# MPPT2.net
KiCad netlist of a schematic drawn in EAGLE
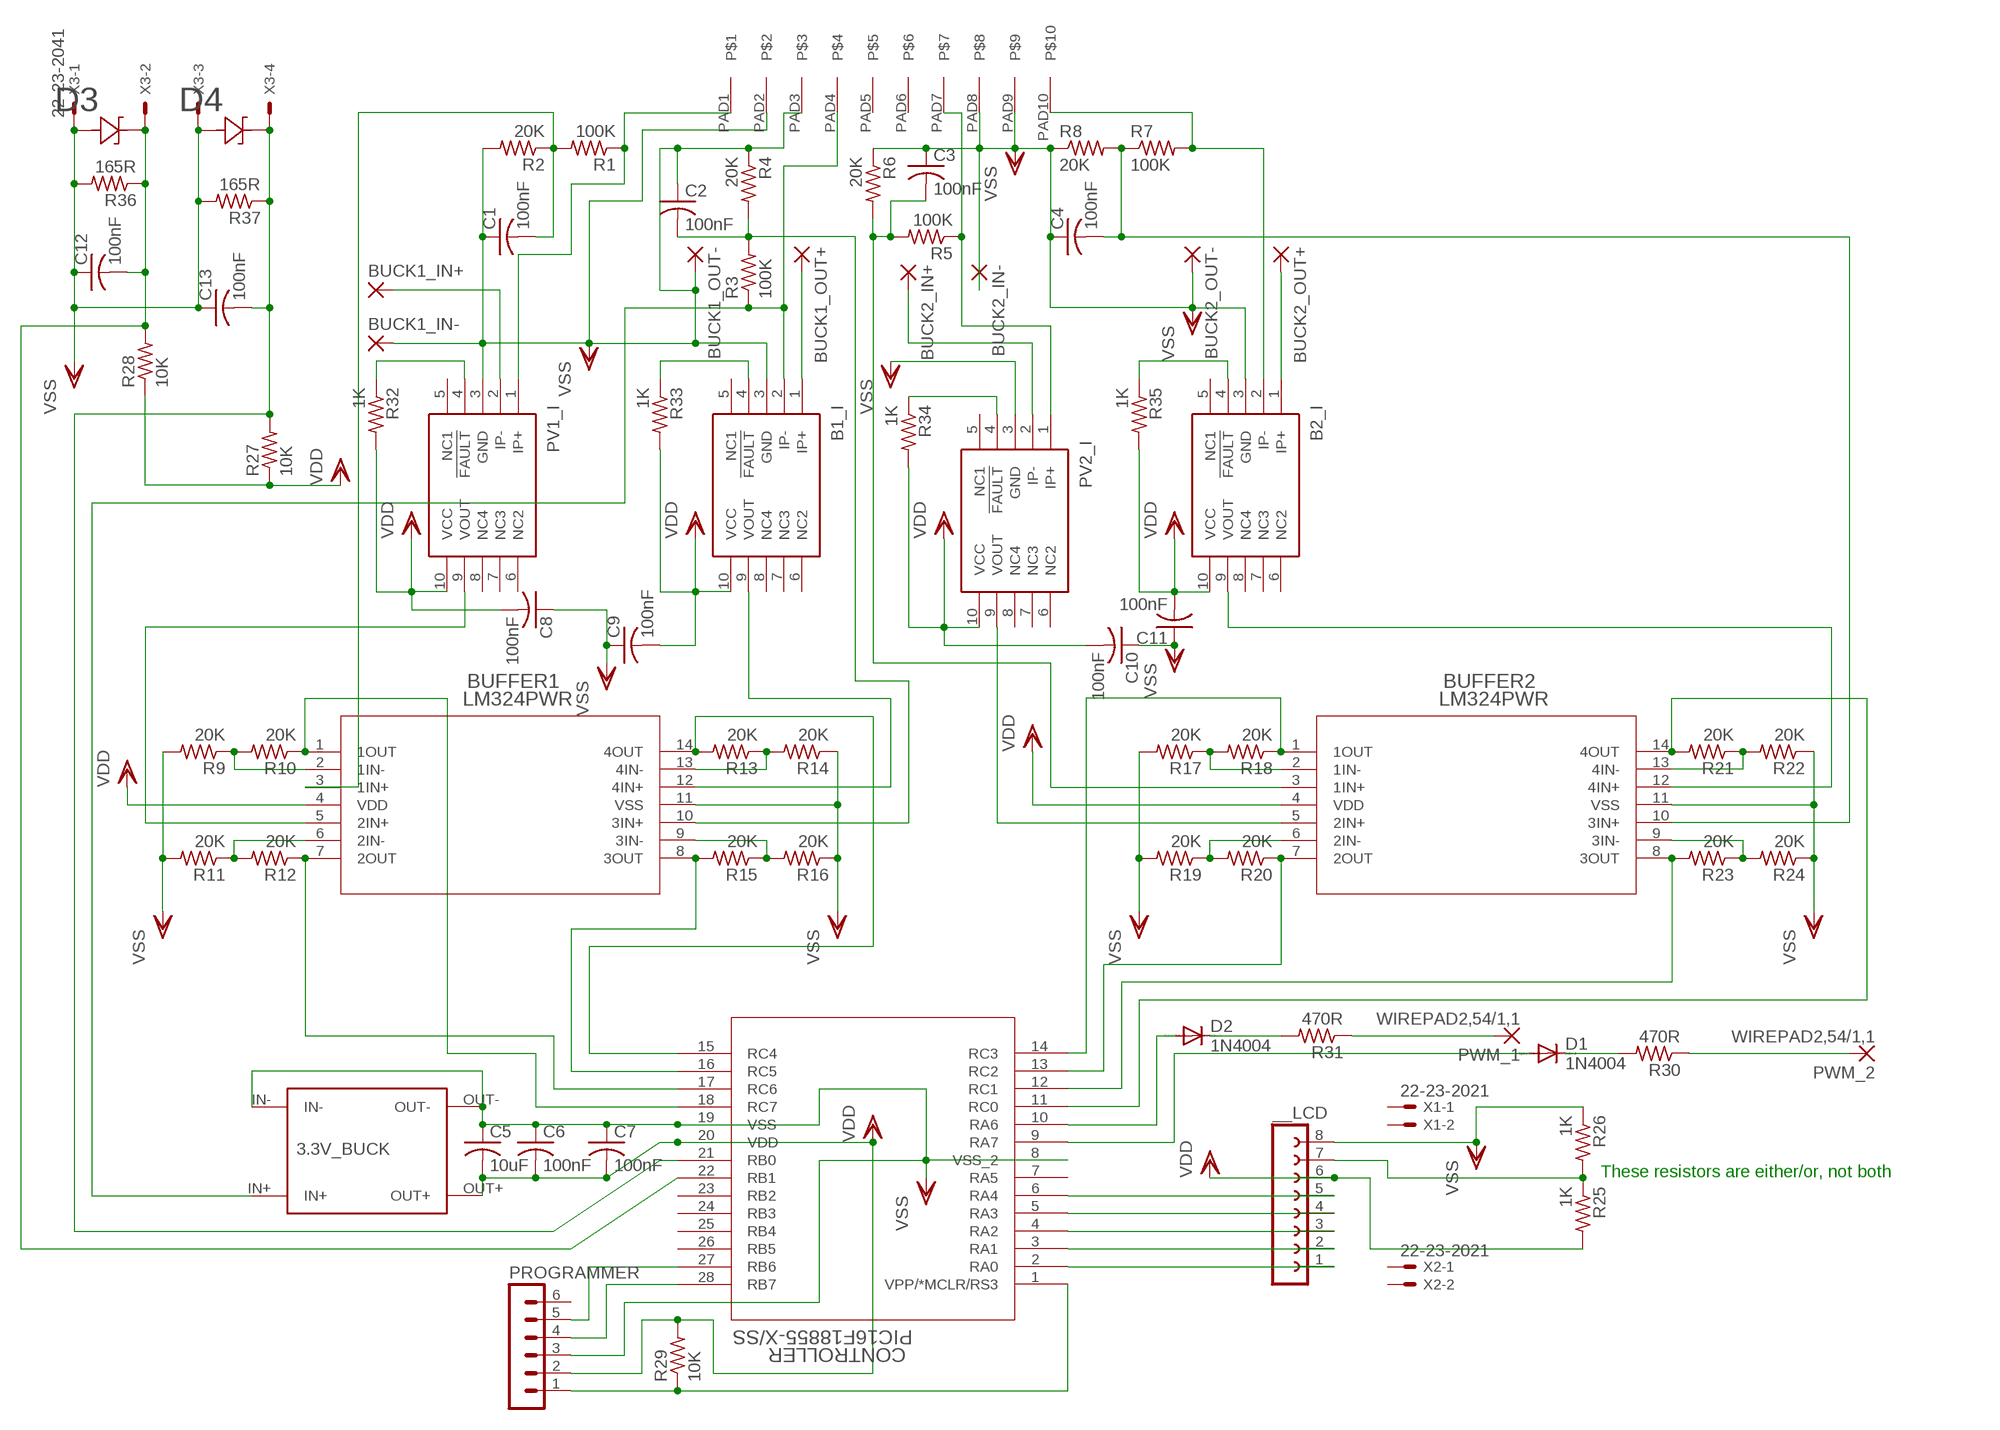
[diagram p0: schematic, sheet 1]

(export (version "E")
  (design (tool "Eeschema 10.0.6"))
  (components
    (comp (ref "3.3V_BUCK")
      (value "TINY_BUCK")
      (footprint "eagle-import:TINY_BUCK")
      (libsource (lib "eagle-import") (part "TINY_BUCK"))
    )
    (comp (ref "B1_I")
      (value "ACS711KEXLT-15AB-T")
      (footprint "eagle-import:EX-PACKAGE")
      (libsource (lib "eagle-import") (part "ACS711KEXLT-15AB-T"))
    )
    (comp (ref "B2_I")
      (value "ACS711KEXLT-15AB-T")
      (footprint "eagle-import:EX-PACKAGE")
      (libsource (lib "eagle-import") (part "ACS711KEXLT-15AB-T"))
    )
    (comp (ref "BUCK1_IN+")
      (value "3,81/1,4")
      (footprint "eagle-import:3,81_1,4")
      (libsource (lib "eagle-import") (part "3,81/1,4"))
    )
    (comp (ref "BUCK1_IN-")
      (value "3,81/1,4")
      (footprint "eagle-import:3,81_1,4")
      (libsource (lib "eagle-import") (part "3,81/1,4"))
    )
    (comp (ref "BUCK1_OUT+")
      (value "3,81/1,4")
      (footprint "eagle-import:3,81_1,4")
      (libsource (lib "eagle-import") (part "3,81/1,4"))
    )
    (comp (ref "BUCK1_OUT-")
      (value "3,81/1,4")
      (footprint "eagle-import:3,81_1,4")
      (libsource (lib "eagle-import") (part "3,81/1,4"))
    )
    (comp (ref "BUCK2_IN+")
      (value "3,81/1,4")
      (footprint "eagle-import:3,81_1,4")
      (libsource (lib "eagle-import") (part "3,81/1,4"))
    )
    (comp (ref "BUCK2_IN-")
      (value "3,81/1,4")
      (footprint "eagle-import:3,81_1,4")
      (libsource (lib "eagle-import") (part "3,81/1,4"))
    )
    (comp (ref "BUCK2_OUT+")
      (value "3,81/1,4")
      (footprint "eagle-import:3,81_1,4")
      (libsource (lib "eagle-import") (part "3,81/1,4"))
    )
    (comp (ref "BUCK2_OUT-")
      (value "3,81/1,4")
      (footprint "eagle-import:3,81_1,4")
      (libsource (lib "eagle-import") (part "3,81/1,4"))
    )
    (comp (ref "BUFFER1")
      (value "LM324PWR")
      (footprint "eagle-import:PW14")
      (libsource (lib "eagle-import") (part "LM324PWR"))
    )
    (comp (ref "BUFFER2")
      (value "LM324PWR")
      (footprint "eagle-import:PW14")
      (libsource (lib "eagle-import") (part "LM324PWR"))
    )
    (comp (ref "C1")
      (value "100nF")
      (footprint "eagle-import:C0603")
      (libsource (lib "eagle-import") (part "C-USC0603"))
    )
    (comp (ref "C2")
      (value "100nF")
      (footprint "eagle-import:C0603")
      (libsource (lib "eagle-import") (part "C-USC0603"))
    )
    (comp (ref "C3")
      (value "100nF")
      (footprint "eagle-import:C0603")
      (libsource (lib "eagle-import") (part "C-USC0603"))
    )
    (comp (ref "C4")
      (value "100nF")
      (footprint "eagle-import:C0603")
      (libsource (lib "eagle-import") (part "C-USC0603"))
    )
    (comp (ref "C5")
      (value "10uF")
      (footprint "eagle-import:C0603")
      (libsource (lib "eagle-import") (part "C-USC0603"))
    )
    (comp (ref "C6")
      (value "100nF")
      (footprint "eagle-import:C0603")
      (libsource (lib "eagle-import") (part "C-USC0603"))
    )
    (comp (ref "C7")
      (value "100nF")
      (footprint "eagle-import:C0603")
      (libsource (lib "eagle-import") (part "C-USC0603"))
    )
    (comp (ref "C8")
      (value "100nF")
      (footprint "eagle-import:C0603")
      (libsource (lib "eagle-import") (part "C-USC0603"))
    )
    (comp (ref "C9")
      (value "100nF")
      (footprint "eagle-import:C0603")
      (libsource (lib "eagle-import") (part "C-USC0603"))
    )
    (comp (ref "C10")
      (value "100nF")
      (footprint "eagle-import:C0603")
      (libsource (lib "eagle-import") (part "C-USC0603"))
    )
    (comp (ref "C11")
      (value "100nF")
      (footprint "eagle-import:C0603")
      (libsource (lib "eagle-import") (part "C-USC0603"))
    )
    (comp (ref "C12")
      (value "100nF")
      (footprint "eagle-import:C0603")
      (libsource (lib "eagle-import") (part "C-USC0603"))
    )
    (comp (ref "C13")
      (value "100nF")
      (footprint "eagle-import:C0603")
      (libsource (lib "eagle-import") (part "C-USC0603"))
    )
    (comp (ref "CONTROLLER")
      (value "PIC16F18855-X/SS")
      (footprint "eagle-import:SSOP28_MC")
      (fields
        (field (name "MANUFACTURER_PART_NUMBER") "pic16f18855-x/ss")
        (field (name "COPYRIGHT") "Copyright (C) 2016 Accelerated Designs. All rights reserved")
      )
      (libsource (lib "eagle-import") (part "PIC16F18855-X/SS"))
    )
    (comp (ref "D1")
      (value "1N4004")
      (footprint "eagle-import:DO41-10")
      (libsource (lib "eagle-import") (part "1N4004"))
    )
    (comp (ref "D2")
      (value "1N4004")
      (footprint "eagle-import:DO41-10")
      (libsource (lib "eagle-import") (part "1N4004"))
    )
    (comp (ref "D3")
      (value "CZRU52C3V3")
      (footprint "eagle-import:CZRU")
      (libsource (lib "eagle-import") (part "CZRU52C3V3"))
    )
    (comp (ref "D4")
      (value "CZRU52C3V3")
      (footprint "eagle-import:CZRU")
      (libsource (lib "eagle-import") (part "CZRU52C3V3"))
    )
    (comp (ref "PROGRAMMER")
      (value "MA06-1")
      (footprint "eagle-import:MA06-1")
      (libsource (lib "eagle-import") (part "MA06-1"))
    )
    (comp (ref "PV1_I")
      (value "ACS711KEXLT-15AB-T")
      (footprint "eagle-import:EX-PACKAGE")
      (libsource (lib "eagle-import") (part "ACS711KEXLT-15AB-T"))
    )
    (comp (ref "PV2_I")
      (value "ACS711KEXLT-15AB-T")
      (footprint "eagle-import:EX-PACKAGE")
      (libsource (lib "eagle-import") (part "ACS711KEXLT-15AB-T"))
    )
    (comp (ref "PWM_1")
      (value "WIREPAD2,54/1,1")
      (footprint "eagle-import:2,54_1,1")
      (libsource (lib "eagle-import") (part "WIREPAD2,54/1,1"))
    )
    (comp (ref "PWM_2")
      (value "WIREPAD2,54/1,1")
      (footprint "eagle-import:2,54_1,1")
      (libsource (lib "eagle-import") (part "WIREPAD2,54/1,1"))
    )
    (comp (ref "R1")
      (value "100K")
      (footprint "eagle-import:R0603")
      (libsource (lib "eagle-import") (part "resistor_R-US_R0603"))
    )
    (comp (ref "R2")
      (value "20K")
      (footprint "eagle-import:R0603")
      (libsource (lib "eagle-import") (part "resistor_R-US_R0603"))
    )
    (comp (ref "R3")
      (value "100K")
      (footprint "eagle-import:R0603")
      (libsource (lib "eagle-import") (part "resistor_R-US_R0603"))
    )
    (comp (ref "R4")
      (value "20K")
      (footprint "eagle-import:R0603")
      (libsource (lib "eagle-import") (part "resistor_R-US_R0603"))
    )
    (comp (ref "R5")
      (value "100K")
      (footprint "eagle-import:R0603")
      (libsource (lib "eagle-import") (part "resistor_R-US_R0603"))
    )
    (comp (ref "R6")
      (value "20K")
      (footprint "eagle-import:R0603")
      (libsource (lib "eagle-import") (part "resistor_R-US_R0603"))
    )
    (comp (ref "R7")
      (value "100K")
      (footprint "eagle-import:R0603")
      (libsource (lib "eagle-import") (part "resistor_R-US_R0603"))
    )
    (comp (ref "R8")
      (value "20K")
      (footprint "eagle-import:R0603")
      (libsource (lib "eagle-import") (part "resistor_R-US_R0603"))
    )
    (comp (ref "R9")
      (value "20K")
      (footprint "eagle-import:R0603")
      (libsource (lib "eagle-import") (part "resistor_R-US_R0603"))
    )
    (comp (ref "R10")
      (value "20K")
      (footprint "eagle-import:R0603")
      (libsource (lib "eagle-import") (part "resistor_R-US_R0603"))
    )
    (comp (ref "R11")
      (value "20K")
      (footprint "eagle-import:R0603")
      (libsource (lib "eagle-import") (part "resistor_R-US_R0603"))
    )
    (comp (ref "R12")
      (value "20K")
      (footprint "eagle-import:R0603")
      (libsource (lib "eagle-import") (part "resistor_R-US_R0603"))
    )
    (comp (ref "R13")
      (value "20K")
      (footprint "eagle-import:R0603")
      (libsource (lib "eagle-import") (part "resistor_R-US_R0603"))
    )
    (comp (ref "R14")
      (value "20K")
      (footprint "eagle-import:R0603")
      (libsource (lib "eagle-import") (part "resistor_R-US_R0603"))
    )
    (comp (ref "R15")
      (value "20K")
      (footprint "eagle-import:R0603")
      (libsource (lib "eagle-import") (part "resistor_R-US_R0603"))
    )
    (comp (ref "R16")
      (value "20K")
      (footprint "eagle-import:R0603")
      (libsource (lib "eagle-import") (part "resistor_R-US_R0603"))
    )
    (comp (ref "R17")
      (value "20K")
      (footprint "eagle-import:R0603")
      (libsource (lib "eagle-import") (part "resistor_R-US_R0603"))
    )
    (comp (ref "R18")
      (value "20K")
      (footprint "eagle-import:R0603")
      (libsource (lib "eagle-import") (part "resistor_R-US_R0603"))
    )
    (comp (ref "R19")
      (value "20K")
      (footprint "eagle-import:R0603")
      (libsource (lib "eagle-import") (part "resistor_R-US_R0603"))
    )
    (comp (ref "R20")
      (value "20K")
      (footprint "eagle-import:R0603")
      (libsource (lib "eagle-import") (part "resistor_R-US_R0603"))
    )
    (comp (ref "R21")
      (value "20K")
      (footprint "eagle-import:R0603")
      (libsource (lib "eagle-import") (part "resistor_R-US_R0603"))
    )
    (comp (ref "R22")
      (value "20K")
      (footprint "eagle-import:R0603")
      (libsource (lib "eagle-import") (part "resistor_R-US_R0603"))
    )
    (comp (ref "R23")
      (value "20K")
      (footprint "eagle-import:R0603")
      (libsource (lib "eagle-import") (part "resistor_R-US_R0603"))
    )
    (comp (ref "R24")
      (value "20K")
      (footprint "eagle-import:R0603")
      (libsource (lib "eagle-import") (part "resistor_R-US_R0603"))
    )
    (comp (ref "R25")
      (value "1K")
      (footprint "eagle-import:R0603")
      (libsource (lib "eagle-import") (part "resistor_R-US_R0603"))
    )
    (comp (ref "R26")
      (value "1K")
      (footprint "eagle-import:R0603")
      (libsource (lib "eagle-import") (part "resistor_R-US_R0603"))
    )
    (comp (ref "R27")
      (value "10K")
      (footprint "eagle-import:R1206")
      (libsource (lib "eagle-import") (part "R-US_R1206"))
    )
    (comp (ref "R28")
      (value "10K")
      (footprint "eagle-import:R0603")
      (libsource (lib "eagle-import") (part "resistor_R-US_R0603"))
    )
    (comp (ref "R29")
      (value "10K")
      (footprint "eagle-import:R0603")
      (libsource (lib "eagle-import") (part "resistor_R-US_R0603"))
    )
    (comp (ref "R30")
      (value "470R")
      (footprint "eagle-import:R0603")
      (libsource (lib "eagle-import") (part "resistor_R-US_R0603"))
    )
    (comp (ref "R31")
      (value "470R")
      (footprint "eagle-import:R1206")
      (libsource (lib "eagle-import") (part "resistor_R-US_R1206"))
    )
    (comp (ref "R32")
      (value "1K")
      (footprint "eagle-import:R0603")
      (libsource (lib "eagle-import") (part "resistor_R-US_R0603"))
    )
    (comp (ref "R33")
      (value "1K")
      (footprint "eagle-import:R0603")
      (libsource (lib "eagle-import") (part "resistor_R-US_R0603"))
    )
    (comp (ref "R34")
      (value "1K")
      (footprint "eagle-import:R0603")
      (libsource (lib "eagle-import") (part "resistor_R-US_R0603"))
    )
    (comp (ref "R35")
      (value "1K")
      (footprint "eagle-import:R0603")
      (libsource (lib "eagle-import") (part "resistor_R-US_R0603"))
    )
    (comp (ref "R36")
      (value "165R")
      (footprint "eagle-import:R0603")
      (libsource (lib "eagle-import") (part "resistor_R-US_R0603"))
    )
    (comp (ref "R37")
      (value "165R")
      (footprint "eagle-import:R0603")
      (libsource (lib "eagle-import") (part "resistor_R-US_R0603"))
    )
    (comp (ref "U$1")
      (value "CONN-KF2EDG-10(5.08)E-BAYPLUGGABLECONNECTORS")
      (footprint "eagle-import:CONN-KF2EDG-10(5.08)")
      (libsource (lib "eagle-import") (part "CONN-KF2EDG-10(5.08)E-BAYPLUGGABLECONNECTORS"))
    )
    (comp (ref "X1")
      (value "22-23-2021")
      (footprint "eagle-import:22-23-2021")
      (fields (field (name "MF") "MOLEX"))
      (libsource (lib "eagle-import") (part "22-23-2021"))
    )
    (comp (ref "X2")
      (value "22-23-2021")
      (footprint "eagle-import:22-23-2021")
      (fields (field (name "MF") "MOLEX"))
      (libsource (lib "eagle-import") (part "22-23-2021"))
    )
    (comp (ref "X3")
      (value "22-23-2041")
      (footprint "eagle-import:22-23-2041")
      (fields (field (name "MF") "MOLEX"))
      (libsource (lib "eagle-import") (part "22-23-2041"))
    )
    (comp (ref "__LCD")
      (value "FE08-1")
      (footprint "eagle-import:FE08")
      (libsource (lib "eagle-import") (part "FE08-1"))
    )
  )
  (nets
    (net (code "1") (name "Net-(B1_I-IP+)") (class "Default")
      (node (ref "B1_I") (pin "1") (pinfunction "IP+_1") (pintype "bidirectional"))
      (node (ref "BUCK1_OUT+") (pin "1") (pinfunction "P_1") (pintype "passive"))
    )
    (net (code "2") (name "Net-(B1_I-IP-)") (class "Default")
      (node (ref "3.3V_BUCK") (pin "IN+") (pinfunction "IN+_IN+") (pintype "power_in"))
      (node (ref "B1_I") (pin "2") (pinfunction "IP-_2") (pintype "bidirectional"))
      (node (ref "R3") (pin "1") (pinfunction "1_1") (pintype "passive"))
      (node (ref "U$1") (pin "PAD4") (pinfunction "P$4_PAD4") (pintype "bidirectional"))
    )
    (net (code "3") (name "Net-(B1_I-VOUT)") (class "Default")
      (node (ref "B1_I") (pin "9") (pinfunction "VOUT_9") (pintype "bidirectional"))
      (node (ref "BUFFER1") (pin "12") (pinfunction "4IN+_12") (pintype "input"))
    )
    (net (code "4") (name "Net-(B1_I-~{FAULT})") (class "Default")
      (node (ref "B1_I") (pin "4") (pinfunction "~{FAULT}_4") (pintype "bidirectional"))
      (node (ref "R33") (pin "1") (pinfunction "1_1") (pintype "passive"))
    )
    (net (code "5") (name "Net-(B2_I-IP+)") (class "Default")
      (node (ref "B2_I") (pin "1") (pinfunction "IP+_1") (pintype "bidirectional"))
      (node (ref "BUCK2_OUT+") (pin "1") (pinfunction "P_1") (pintype "passive"))
    )
    (net (code "6") (name "Net-(B2_I-IP-)") (class "Default")
      (node (ref "B2_I") (pin "2") (pinfunction "IP-_2") (pintype "bidirectional"))
      (node (ref "R7") (pin "2") (pinfunction "2_2") (pintype "passive"))
      (node (ref "U$1") (pin "PAD10") (pinfunction "P$10_PAD10") (pintype "bidirectional"))
    )
    (net (code "7") (name "Net-(B2_I-VOUT)") (class "Default")
      (node (ref "B2_I") (pin "9") (pinfunction "VOUT_9") (pintype "bidirectional"))
      (node (ref "BUFFER2") (pin "12") (pinfunction "4IN+_12") (pintype "input"))
    )
    (net (code "8") (name "Net-(B2_I-~{FAULT})") (class "Default")
      (node (ref "B2_I") (pin "4") (pinfunction "~{FAULT}_4") (pintype "bidirectional"))
      (node (ref "R35") (pin "1") (pinfunction "1_1") (pintype "passive"))
    )
    (net (code "9") (name "Net-(BUCK1_IN+-P)") (class "Default")
      (node (ref "BUCK1_IN+") (pin "1") (pinfunction "P_1") (pintype "passive"))
      (node (ref "PV1_I") (pin "2") (pinfunction "IP-_2") (pintype "bidirectional"))
    )
    (net (code "10") (name "Net-(BUCK2_IN+-P)") (class "Default")
      (node (ref "BUCK2_IN+") (pin "1") (pinfunction "P_1") (pintype "passive"))
      (node (ref "PV2_I") (pin "2") (pinfunction "IP-_2") (pintype "bidirectional"))
    )
    (net (code "11") (name "Net-(BUFFER1-1IN+)") (class "Default")
      (node (ref "BUFFER1") (pin "3") (pinfunction "1IN+_3") (pintype "input"))
      (node (ref "C1") (pin "2") (pinfunction "2_2") (pintype "passive"))
      (node (ref "R1") (pin "2") (pinfunction "2_2") (pintype "passive"))
      (node (ref "R2") (pin "1") (pinfunction "1_1") (pintype "passive"))
    )
    (net (code "12") (name "Net-(BUFFER1-1IN-)") (class "Default")
      (node (ref "BUFFER1") (pin "2") (pinfunction "1IN-_2") (pintype "input"))
      (node (ref "R10") (pin "2") (pinfunction "2_2") (pintype "passive"))
      (node (ref "R9") (pin "1") (pinfunction "1_1") (pintype "passive"))
    )
    (net (code "13") (name "Net-(BUFFER1-1OUT)") (class "Default")
      (node (ref "BUFFER1") (pin "1") (pinfunction "1OUT_1") (pintype "output"))
      (node (ref "CONTROLLER") (pin "18") (pinfunction "RC7_18") (pintype "bidirectional"))
      (node (ref "R10") (pin "1") (pinfunction "1_1") (pintype "passive"))
    )
    (net (code "14") (name "Net-(BUFFER1-2IN+)") (class "Default")
      (node (ref "BUFFER1") (pin "5") (pinfunction "2IN+_5") (pintype "input"))
      (node (ref "PV1_I") (pin "9") (pinfunction "VOUT_9") (pintype "bidirectional"))
    )
    (net (code "15") (name "Net-(BUFFER1-2IN-)") (class "Default")
      (node (ref "BUFFER1") (pin "6") (pinfunction "2IN-_6") (pintype "input"))
      (node (ref "R11") (pin "1") (pinfunction "1_1") (pintype "passive"))
      (node (ref "R12") (pin "2") (pinfunction "2_2") (pintype "passive"))
    )
    (net (code "16") (name "Net-(BUFFER1-2OUT)") (class "Default")
      (node (ref "BUFFER1") (pin "7") (pinfunction "2OUT_7") (pintype "output"))
      (node (ref "CONTROLLER") (pin "17") (pinfunction "RC6_17") (pintype "bidirectional"))
      (node (ref "R12") (pin "1") (pinfunction "1_1") (pintype "passive"))
    )
    (net (code "17") (name "Net-(BUFFER1-3IN+)") (class "Default")
      (node (ref "BUFFER1") (pin "10") (pinfunction "3IN+_10") (pintype "input"))
      (node (ref "C2") (pin "2") (pinfunction "2_2") (pintype "passive"))
      (node (ref "R3") (pin "2") (pinfunction "2_2") (pintype "passive"))
      (node (ref "R4") (pin "2") (pinfunction "2_2") (pintype "passive"))
    )
    (net (code "18") (name "Net-(BUFFER1-3IN-)") (class "Default")
      (node (ref "BUFFER1") (pin "9") (pinfunction "3IN-_9") (pintype "input"))
      (node (ref "R15") (pin "1") (pinfunction "1_1") (pintype "passive"))
      (node (ref "R16") (pin "2") (pinfunction "2_2") (pintype "passive"))
    )
    (net (code "19") (name "Net-(BUFFER1-3OUT)") (class "Default")
      (node (ref "BUFFER1") (pin "8") (pinfunction "3OUT_8") (pintype "output"))
      (node (ref "CONTROLLER") (pin "16") (pinfunction "RC5_16") (pintype "bidirectional"))
      (node (ref "R15") (pin "2") (pinfunction "2_2") (pintype "passive"))
    )
    (net (code "20") (name "Net-(BUFFER1-4IN-)") (class "Default")
      (node (ref "BUFFER1") (pin "13") (pinfunction "4IN-_13") (pintype "input"))
      (node (ref "R13") (pin "1") (pinfunction "1_1") (pintype "passive"))
      (node (ref "R14") (pin "2") (pinfunction "2_2") (pintype "passive"))
    )
    (net (code "21") (name "Net-(BUFFER1-4OUT)") (class "Default")
      (node (ref "BUFFER1") (pin "14") (pinfunction "4OUT_14") (pintype "output"))
      (node (ref "CONTROLLER") (pin "15") (pinfunction "RC4_15") (pintype "bidirectional"))
      (node (ref "R13") (pin "2") (pinfunction "2_2") (pintype "passive"))
    )
    (net (code "22") (name "Net-(BUFFER2-1IN+)") (class "Default")
      (node (ref "BUFFER2") (pin "3") (pinfunction "1IN+_3") (pintype "input"))
      (node (ref "C3") (pin "2") (pinfunction "2_2") (pintype "passive"))
      (node (ref "R5") (pin "2") (pinfunction "2_2") (pintype "passive"))
      (node (ref "R6") (pin "2") (pinfunction "2_2") (pintype "passive"))
    )
    (net (code "23") (name "Net-(BUFFER2-1IN-)") (class "Default")
      (node (ref "BUFFER2") (pin "2") (pinfunction "1IN-_2") (pintype "input"))
      (node (ref "R17") (pin "1") (pinfunction "1_1") (pintype "passive"))
      (node (ref "R18") (pin "2") (pinfunction "2_2") (pintype "passive"))
    )
    (net (code "24") (name "Net-(BUFFER2-1OUT)") (class "Default")
      (node (ref "BUFFER2") (pin "1") (pinfunction "1OUT_1") (pintype "output"))
      (node (ref "CONTROLLER") (pin "14") (pinfunction "RC3_14") (pintype "bidirectional"))
      (node (ref "R18") (pin "1") (pinfunction "1_1") (pintype "passive"))
    )
    (net (code "25") (name "Net-(BUFFER2-2IN+)") (class "Default")
      (node (ref "BUFFER2") (pin "5") (pinfunction "2IN+_5") (pintype "input"))
      (node (ref "PV2_I") (pin "9") (pinfunction "VOUT_9") (pintype "bidirectional"))
    )
    (net (code "26") (name "Net-(BUFFER2-2IN-)") (class "Default")
      (node (ref "BUFFER2") (pin "6") (pinfunction "2IN-_6") (pintype "input"))
      (node (ref "R19") (pin "1") (pinfunction "1_1") (pintype "passive"))
      (node (ref "R20") (pin "2") (pinfunction "2_2") (pintype "passive"))
    )
    (net (code "27") (name "Net-(BUFFER2-2OUT)") (class "Default")
      (node (ref "BUFFER2") (pin "7") (pinfunction "2OUT_7") (pintype "output"))
      (node (ref "CONTROLLER") (pin "13") (pinfunction "RC2_13") (pintype "bidirectional"))
      (node (ref "R20") (pin "1") (pinfunction "1_1") (pintype "passive"))
    )
    (net (code "28") (name "Net-(BUFFER2-3IN+)") (class "Default")
      (node (ref "BUFFER2") (pin "10") (pinfunction "3IN+_10") (pintype "input"))
      (node (ref "C4") (pin "2") (pinfunction "2_2") (pintype "passive"))
      (node (ref "R7") (pin "1") (pinfunction "1_1") (pintype "passive"))
      (node (ref "R8") (pin "2") (pinfunction "2_2") (pintype "passive"))
    )
    (net (code "29") (name "Net-(BUFFER2-3IN-)") (class "Default")
      (node (ref "BUFFER2") (pin "9") (pinfunction "3IN-_9") (pintype "input"))
      (node (ref "R23") (pin "1") (pinfunction "1_1") (pintype "passive"))
      (node (ref "R24") (pin "2") (pinfunction "2_2") (pintype "passive"))
    )
    (net (code "30") (name "Net-(BUFFER2-3OUT)") (class "Default")
      (node (ref "BUFFER2") (pin "8") (pinfunction "3OUT_8") (pintype "output"))
      (node (ref "CONTROLLER") (pin "12") (pinfunction "RC1_12") (pintype "bidirectional"))
      (node (ref "R23") (pin "2") (pinfunction "2_2") (pintype "passive"))
    )
    (net (code "31") (name "Net-(BUFFER2-4IN-)") (class "Default")
      (node (ref "BUFFER2") (pin "13") (pinfunction "4IN-_13") (pintype "input"))
      (node (ref "R21") (pin "1") (pinfunction "1_1") (pintype "passive"))
      (node (ref "R22") (pin "2") (pinfunction "2_2") (pintype "passive"))
    )
    (net (code "32") (name "Net-(BUFFER2-4OUT)") (class "Default")
      (node (ref "BUFFER2") (pin "14") (pinfunction "4OUT_14") (pintype "output"))
      (node (ref "CONTROLLER") (pin "11") (pinfunction "RC0_11") (pintype "bidirectional"))
      (node (ref "R21") (pin "2") (pinfunction "2_2") (pintype "passive"))
    )
    (net (code "33") (name "Net-(CONTROLLER-RA0)") (class "Default")
      (node (ref "CONTROLLER") (pin "2") (pinfunction "RA0_2") (pintype "bidirectional"))
      (node (ref "__LCD") (pin "1") (pinfunction "1_1") (pintype "passive"))
    )
    (net (code "34") (name "Net-(CONTROLLER-RA1)") (class "Default")
      (node (ref "CONTROLLER") (pin "3") (pinfunction "RA1_3") (pintype "bidirectional"))
      (node (ref "__LCD") (pin "2") (pinfunction "2_2") (pintype "passive"))
    )
    (net (code "35") (name "Net-(CONTROLLER-RA2)") (class "Default")
      (node (ref "CONTROLLER") (pin "4") (pinfunction "RA2_4") (pintype "bidirectional"))
      (node (ref "__LCD") (pin "3") (pinfunction "3_3") (pintype "passive"))
    )
    (net (code "36") (name "Net-(CONTROLLER-RA3)") (class "Default")
      (node (ref "CONTROLLER") (pin "5") (pinfunction "RA3_5") (pintype "bidirectional"))
      (node (ref "__LCD") (pin "4") (pinfunction "4_4") (pintype "passive"))
    )
    (net (code "37") (name "Net-(CONTROLLER-RA4)") (class "Default")
      (node (ref "CONTROLLER") (pin "6") (pinfunction "RA4_6") (pintype "bidirectional"))
      (node (ref "__LCD") (pin "5") (pinfunction "5_5") (pintype "passive"))
    )
    (net (code "38") (name "Net-(CONTROLLER-RA6)") (class "Default")
      (node (ref "CONTROLLER") (pin "10") (pinfunction "RA6_10") (pintype "bidirectional"))
      (node (ref "D2") (pin "A") (pinfunction "A_A") (pintype "passive"))
    )
    (net (code "39") (name "Net-(CONTROLLER-RA7)") (class "Default")
      (node (ref "CONTROLLER") (pin "9") (pinfunction "RA7_9") (pintype "bidirectional"))
      (node (ref "D1") (pin "A") (pinfunction "A_A") (pintype "passive"))
    )
    (net (code "40") (name "Net-(CONTROLLER-RB0)") (class "Default")
      (node (ref "C13") (pin "2") (pinfunction "2_2") (pintype "passive"))
      (node (ref "CONTROLLER") (pin "21") (pinfunction "RB0_21") (pintype "bidirectional"))
      (node (ref "D4") (pin "1") (pinfunction "11_1") (pintype "passive"))
      (node (ref "R27") (pin "2") (pinfunction "2_2") (pintype "passive"))
      (node (ref "R37") (pin "1") (pinfunction "1_1") (pintype "passive"))
      (node (ref "X3") (pin "4") (pinfunction "S_4") (pintype "passive"))
    )
    (net (code "41") (name "Net-(CONTROLLER-RB1)") (class "Default")
      (node (ref "C12") (pin "2") (pinfunction "2_2") (pintype "passive"))
      (node (ref "CONTROLLER") (pin "22") (pinfunction "RB1_22") (pintype "bidirectional"))
      (node (ref "D3") (pin "1") (pinfunction "11_1") (pintype "passive"))
      (node (ref "R28") (pin "2") (pinfunction "2_2") (pintype "passive"))
      (node (ref "R36") (pin "1") (pinfunction "1_1") (pintype "passive"))
      (node (ref "X3") (pin "2") (pinfunction "S_2") (pintype "passive"))
    )
    (net (code "42") (name "Net-(CONTROLLER-RB6)") (class "Default")
      (node (ref "CONTROLLER") (pin "27") (pinfunction "RB6_27") (pintype "bidirectional"))
      (node (ref "PROGRAMMER") (pin "5") (pinfunction "5_5") (pintype "passive"))
    )
    (net (code "43") (name "Net-(CONTROLLER-RB7)") (class "Default")
      (node (ref "CONTROLLER") (pin "28") (pinfunction "RB7_28") (pintype "bidirectional"))
      (node (ref "PROGRAMMER") (pin "4") (pinfunction "4_4") (pintype "passive"))
    )
    (net (code "44") (name "Net-(CONTROLLER-VPP{slash}*MCLR{slash}RS3)") (class "Default")
      (node (ref "CONTROLLER") (pin "1") (pinfunction "VPP/*MCLR/RS3_1") (pintype "bidirectional"))
      (node (ref "PROGRAMMER") (pin "1") (pinfunction "1_1") (pintype "passive"))
      (node (ref "R29") (pin "1") (pinfunction "1_1") (pintype "passive"))
    )
    (net (code "45") (name "Net-(D1-PadC)") (class "Default")
      (node (ref "D1") (pin "C") (pinfunction "C_C") (pintype "passive"))
      (node (ref "R30") (pin "2") (pinfunction "2_2") (pintype "passive"))
    )
    (net (code "46") (name "Net-(D2-PadC)") (class "Default")
      (node (ref "D2") (pin "C") (pinfunction "C_C") (pintype "passive"))
      (node (ref "R31") (pin "2") (pinfunction "2_2") (pintype "passive"))
    )
    (net (code "47") (name "Net-(PV1_I-IP+)") (class "Default")
      (node (ref "PV1_I") (pin "1") (pinfunction "IP+_1") (pintype "bidirectional"))
      (node (ref "R1") (pin "1") (pinfunction "1_1") (pintype "passive"))
      (node (ref "U$1") (pin "PAD1") (pinfunction "P$1_PAD1") (pintype "bidirectional"))
    )
    (net (code "48") (name "Net-(PV1_I-~{FAULT})") (class "Default")
      (node (ref "PV1_I") (pin "4") (pinfunction "~{FAULT}_4") (pintype "bidirectional"))
      (node (ref "R32") (pin "1") (pinfunction "1_1") (pintype "passive"))
    )
    (net (code "49") (name "Net-(PV2_I-IP+)") (class "Default")
      (node (ref "PV2_I") (pin "1") (pinfunction "IP+_1") (pintype "bidirectional"))
      (node (ref "R5") (pin "1") (pinfunction "1_1") (pintype "passive"))
      (node (ref "U$1") (pin "PAD7") (pinfunction "P$7_PAD7") (pintype "bidirectional"))
    )
    (net (code "50") (name "Net-(PV2_I-~{FAULT})") (class "Default")
      (node (ref "PV2_I") (pin "4") (pinfunction "~{FAULT}_4") (pintype "bidirectional"))
      (node (ref "R34") (pin "1") (pinfunction "1_1") (pintype "passive"))
    )
    (net (code "51") (name "Net-(PWM_1-P)") (class "Default")
      (node (ref "PWM_1") (pin "1") (pinfunction "P_1") (pintype "passive"))
      (node (ref "R31") (pin "1") (pinfunction "1_1") (pintype "passive"))
    )
    (net (code "52") (name "Net-(PWM_2-P)") (class "Default")
      (node (ref "PWM_2") (pin "1") (pinfunction "P_1") (pintype "passive"))
      (node (ref "R30") (pin "1") (pinfunction "1_1") (pintype "passive"))
    )
    (net (code "53") (name "Net-(R25-Pad1)") (class "Default")
      (node (ref "R25") (pin "1") (pinfunction "1_1") (pintype "passive"))
      (node (ref "R26") (pin "2") (pinfunction "2_2") (pintype "passive"))
      (node (ref "__LCD") (pin "7") (pinfunction "7_7") (pintype "passive"))
    )
    (net (code "54") (name "VDD") (class "Default")
      (node (ref "3.3V_BUCK") (pin "OUT+") (pinfunction "OUT+_OUT+") (pintype "power_in"))
      (node (ref "B1_I") (pin "10") (pinfunction "VCC_10") (pintype "bidirectional"))
      (node (ref "B2_I") (pin "10") (pinfunction "VCC_10") (pintype "bidirectional"))
      (node (ref "BUFFER1") (pin "4") (pinfunction "VDD_4") (pintype "power_in"))
      (node (ref "BUFFER2") (pin "4") (pinfunction "VDD_4") (pintype "power_in"))
      (node (ref "C10") (pin "2") (pinfunction "2_2") (pintype "passive"))
      (node (ref "C11") (pin "2") (pinfunction "2_2") (pintype "passive"))
      (node (ref "C5") (pin "2") (pinfunction "2_2") (pintype "passive"))
      (node (ref "C6") (pin "2") (pinfunction "2_2") (pintype "passive"))
      (node (ref "C7") (pin "2") (pinfunction "2_2") (pintype "passive"))
      (node (ref "C8") (pin "2") (pinfunction "2_2") (pintype "passive"))
      (node (ref "C9") (pin "2") (pinfunction "2_2") (pintype "passive"))
      (node (ref "CONTROLLER") (pin "20") (pinfunction "VDD_20") (pintype "power_in"))
      (node (ref "PROGRAMMER") (pin "2") (pinfunction "2_2") (pintype "passive"))
      (node (ref "PV1_I") (pin "10") (pinfunction "VCC_10") (pintype "bidirectional"))
      (node (ref "PV2_I") (pin "10") (pinfunction "VCC_10") (pintype "bidirectional"))
      (node (ref "R25") (pin "2") (pinfunction "2_2") (pintype "passive"))
      (node (ref "R27") (pin "1") (pinfunction "1_1") (pintype "passive"))
      (node (ref "R28") (pin "1") (pinfunction "1_1") (pintype "passive"))
      (node (ref "R29") (pin "2") (pinfunction "2_2") (pintype "passive"))
      (node (ref "R32") (pin "2") (pinfunction "2_2") (pintype "passive"))
      (node (ref "R33") (pin "2") (pinfunction "2_2") (pintype "passive"))
      (node (ref "R34") (pin "2") (pinfunction "2_2") (pintype "passive"))
      (node (ref "R35") (pin "2") (pinfunction "2_2") (pintype "passive"))
      (node (ref "__LCD") (pin "6") (pinfunction "6_6") (pintype "passive"))
    )
    (net (code "55") (name "VSS") (class "Default")
      (node (ref "3.3V_BUCK") (pin "IN-") (pinfunction "IN-_IN-") (pintype "power_in"))
      (node (ref "3.3V_BUCK") (pin "OUT-") (pinfunction "OUT-_OUT-") (pintype "power_in"))
      (node (ref "B1_I") (pin "3") (pinfunction "GND_3") (pintype "bidirectional"))
      (node (ref "B2_I") (pin "3") (pinfunction "GND_3") (pintype "bidirectional"))
      (node (ref "BUCK1_IN-") (pin "1") (pinfunction "P_1") (pintype "passive"))
      (node (ref "BUCK1_OUT-") (pin "1") (pinfunction "P_1") (pintype "passive"))
      (node (ref "BUCK2_IN-") (pin "1") (pinfunction "P_1") (pintype "passive"))
      (node (ref "BUCK2_OUT-") (pin "1") (pinfunction "P_1") (pintype "passive"))
      (node (ref "BUFFER1") (pin "11") (pinfunction "VSS_11") (pintype "power_in"))
      (node (ref "BUFFER2") (pin "11") (pinfunction "VSS_11") (pintype "power_in"))
      (node (ref "C1") (pin "1") (pinfunction "1_1") (pintype "passive"))
      (node (ref "C10") (pin "1") (pinfunction "1_1") (pintype "passive"))
      (node (ref "C11") (pin "1") (pinfunction "1_1") (pintype "passive"))
      (node (ref "C12") (pin "1") (pinfunction "1_1") (pintype "passive"))
      (node (ref "C13") (pin "1") (pinfunction "1_1") (pintype "passive"))
      (node (ref "C2") (pin "1") (pinfunction "1_1") (pintype "passive"))
      (node (ref "C3") (pin "1") (pinfunction "1_1") (pintype "passive"))
      (node (ref "C4") (pin "1") (pinfunction "1_1") (pintype "passive"))
      (node (ref "C5") (pin "1") (pinfunction "1_1") (pintype "passive"))
      (node (ref "C6") (pin "1") (pinfunction "1_1") (pintype "passive"))
      (node (ref "C7") (pin "1") (pinfunction "1_1") (pintype "passive"))
      (node (ref "C8") (pin "1") (pinfunction "1_1") (pintype "passive"))
      (node (ref "C9") (pin "1") (pinfunction "1_1") (pintype "passive"))
      (node (ref "CONTROLLER") (pin "19") (pinfunction "VSS_19") (pintype "power_in"))
      (node (ref "CONTROLLER") (pin "8") (pinfunction "VSS_2_8") (pintype "power_in"))
      (node (ref "D3") (pin "2") (pinfunction "22_2") (pintype "passive"))
      (node (ref "D4") (pin "2") (pinfunction "22_2") (pintype "passive"))
      (node (ref "PROGRAMMER") (pin "3") (pinfunction "3_3") (pintype "passive"))
      (node (ref "PV1_I") (pin "3") (pinfunction "GND_3") (pintype "bidirectional"))
      (node (ref "PV2_I") (pin "3") (pinfunction "GND_3") (pintype "bidirectional"))
      (node (ref "R11") (pin "2") (pinfunction "2_2") (pintype "passive"))
      (node (ref "R14") (pin "1") (pinfunction "1_1") (pintype "passive"))
      (node (ref "R16") (pin "1") (pinfunction "1_1") (pintype "passive"))
      (node (ref "R17") (pin "2") (pinfunction "2_2") (pintype "passive"))
      (node (ref "R19") (pin "2") (pinfunction "2_2") (pintype "passive"))
      (node (ref "R2") (pin "2") (pinfunction "2_2") (pintype "passive"))
      (node (ref "R22") (pin "1") (pinfunction "1_1") (pintype "passive"))
      (node (ref "R24") (pin "1") (pinfunction "1_1") (pintype "passive"))
      (node (ref "R26") (pin "1") (pinfunction "1_1") (pintype "passive"))
      (node (ref "R36") (pin "2") (pinfunction "2_2") (pintype "passive"))
      (node (ref "R37") (pin "2") (pinfunction "2_2") (pintype "passive"))
      (node (ref "R4") (pin "1") (pinfunction "1_1") (pintype "passive"))
      (node (ref "R6") (pin "1") (pinfunction "1_1") (pintype "passive"))
      (node (ref "R8") (pin "1") (pinfunction "1_1") (pintype "passive"))
      (node (ref "R9") (pin "2") (pinfunction "2_2") (pintype "passive"))
      (node (ref "U$1") (pin "PAD2") (pinfunction "P$2_PAD2") (pintype "bidirectional"))
      (node (ref "U$1") (pin "PAD3") (pinfunction "P$3_PAD3") (pintype "bidirectional"))
      (node (ref "U$1") (pin "PAD8") (pinfunction "P$8_PAD8") (pintype "bidirectional"))
      (node (ref "U$1") (pin "PAD9") (pinfunction "P$9_PAD9") (pintype "bidirectional"))
      (node (ref "X3") (pin "1") (pinfunction "S_1") (pintype "passive"))
      (node (ref "X3") (pin "3") (pinfunction "S_3") (pintype "passive"))
      (node (ref "__LCD") (pin "8") (pinfunction "8_8") (pintype "passive"))
    )
    (net (code "56") (name "unconnected-(B1_I-NC1-Pad5)") (class "Default")
      (node (ref "B1_I") (pin "5") (pinfunction "NC1_5") (pintype "bidirectional"))
    )
    (net (code "57") (name "unconnected-(B1_I-NC2-Pad6)") (class "Default")
      (node (ref "B1_I") (pin "6") (pinfunction "NC2_6") (pintype "bidirectional"))
    )
    (net (code "58") (name "unconnected-(B1_I-NC3-Pad7)") (class "Default")
      (node (ref "B1_I") (pin "7") (pinfunction "NC3_7") (pintype "bidirectional"))
    )
    (net (code "59") (name "unconnected-(B1_I-NC4-Pad8)") (class "Default")
      (node (ref "B1_I") (pin "8") (pinfunction "NC4_8") (pintype "bidirectional"))
    )
    (net (code "60") (name "unconnected-(B2_I-NC1-Pad5)") (class "Default")
      (node (ref "B2_I") (pin "5") (pinfunction "NC1_5") (pintype "bidirectional"))
    )
    (net (code "61") (name "unconnected-(B2_I-NC2-Pad6)") (class "Default")
      (node (ref "B2_I") (pin "6") (pinfunction "NC2_6") (pintype "bidirectional"))
    )
    (net (code "62") (name "unconnected-(B2_I-NC3-Pad7)") (class "Default")
      (node (ref "B2_I") (pin "7") (pinfunction "NC3_7") (pintype "bidirectional"))
    )
    (net (code "63") (name "unconnected-(B2_I-NC4-Pad8)") (class "Default")
      (node (ref "B2_I") (pin "8") (pinfunction "NC4_8") (pintype "bidirectional"))
    )
    (net (code "64") (name "unconnected-(CONTROLLER-RA5-Pad7)") (class "Default")
      (node (ref "CONTROLLER") (pin "7") (pinfunction "RA5_7") (pintype "bidirectional"))
    )
    (net (code "65") (name "unconnected-(CONTROLLER-RB2-Pad23)") (class "Default")
      (node (ref "CONTROLLER") (pin "23") (pinfunction "RB2_23") (pintype "bidirectional"))
    )
    (net (code "66") (name "unconnected-(CONTROLLER-RB3-Pad24)") (class "Default")
      (node (ref "CONTROLLER") (pin "24") (pinfunction "RB3_24") (pintype "bidirectional"))
    )
    (net (code "67") (name "unconnected-(CONTROLLER-RB4-Pad25)") (class "Default")
      (node (ref "CONTROLLER") (pin "25") (pinfunction "RB4_25") (pintype "bidirectional"))
    )
    (net (code "68") (name "unconnected-(CONTROLLER-RB5-Pad26)") (class "Default")
      (node (ref "CONTROLLER") (pin "26") (pinfunction "RB5_26") (pintype "bidirectional"))
    )
    (net (code "69") (name "unconnected-(PROGRAMMER-Pad6)") (class "Default")
      (node (ref "PROGRAMMER") (pin "6") (pinfunction "6_6") (pintype "passive"))
    )
    (net (code "70") (name "unconnected-(PV1_I-NC1-Pad5)") (class "Default")
      (node (ref "PV1_I") (pin "5") (pinfunction "NC1_5") (pintype "bidirectional"))
    )
    (net (code "71") (name "unconnected-(PV1_I-NC2-Pad6)") (class "Default")
      (node (ref "PV1_I") (pin "6") (pinfunction "NC2_6") (pintype "bidirectional"))
    )
    (net (code "72") (name "unconnected-(PV1_I-NC3-Pad7)") (class "Default")
      (node (ref "PV1_I") (pin "7") (pinfunction "NC3_7") (pintype "bidirectional"))
    )
    (net (code "73") (name "unconnected-(PV1_I-NC4-Pad8)") (class "Default")
      (node (ref "PV1_I") (pin "8") (pinfunction "NC4_8") (pintype "bidirectional"))
    )
    (net (code "74") (name "unconnected-(PV2_I-NC1-Pad5)") (class "Default")
      (node (ref "PV2_I") (pin "5") (pinfunction "NC1_5") (pintype "bidirectional"))
    )
    (net (code "75") (name "unconnected-(PV2_I-NC2-Pad6)") (class "Default")
      (node (ref "PV2_I") (pin "6") (pinfunction "NC2_6") (pintype "bidirectional"))
    )
    (net (code "76") (name "unconnected-(PV2_I-NC3-Pad7)") (class "Default")
      (node (ref "PV2_I") (pin "7") (pinfunction "NC3_7") (pintype "bidirectional"))
    )
    (net (code "77") (name "unconnected-(PV2_I-NC4-Pad8)") (class "Default")
      (node (ref "PV2_I") (pin "8") (pinfunction "NC4_8") (pintype "bidirectional"))
    )
    (net (code "78") (name "unconnected-(U$1-P$5-PadPAD5)") (class "Default")
      (node (ref "U$1") (pin "PAD5") (pinfunction "P$5_PAD5") (pintype "bidirectional"))
    )
    (net (code "79") (name "unconnected-(U$1-P$6-PadPAD6)") (class "Default")
      (node (ref "U$1") (pin "PAD6") (pinfunction "P$6_PAD6") (pintype "bidirectional"))
    )
    (net (code "80") (name "unconnected-(X1A-S-Pad1)") (class "Default")
      (node (ref "X1") (pin "1") (pinfunction "S_1") (pintype "passive"))
    )
    (net (code "81") (name "unconnected-(X1B-S-Pad2)") (class "Default")
      (node (ref "X1") (pin "2") (pinfunction "S_2") (pintype "passive"))
    )
    (net (code "82") (name "unconnected-(X2A-S-Pad1)") (class "Default")
      (node (ref "X2") (pin "1") (pinfunction "S_1") (pintype "passive"))
    )
    (net (code "83") (name "unconnected-(X2B-S-Pad2)") (class "Default")
      (node (ref "X2") (pin "2") (pinfunction "S_2") (pintype "passive"))
    )
  )
)
